# sim800L_5.net
KiCad netlist of a schematic drawn in EAGLE
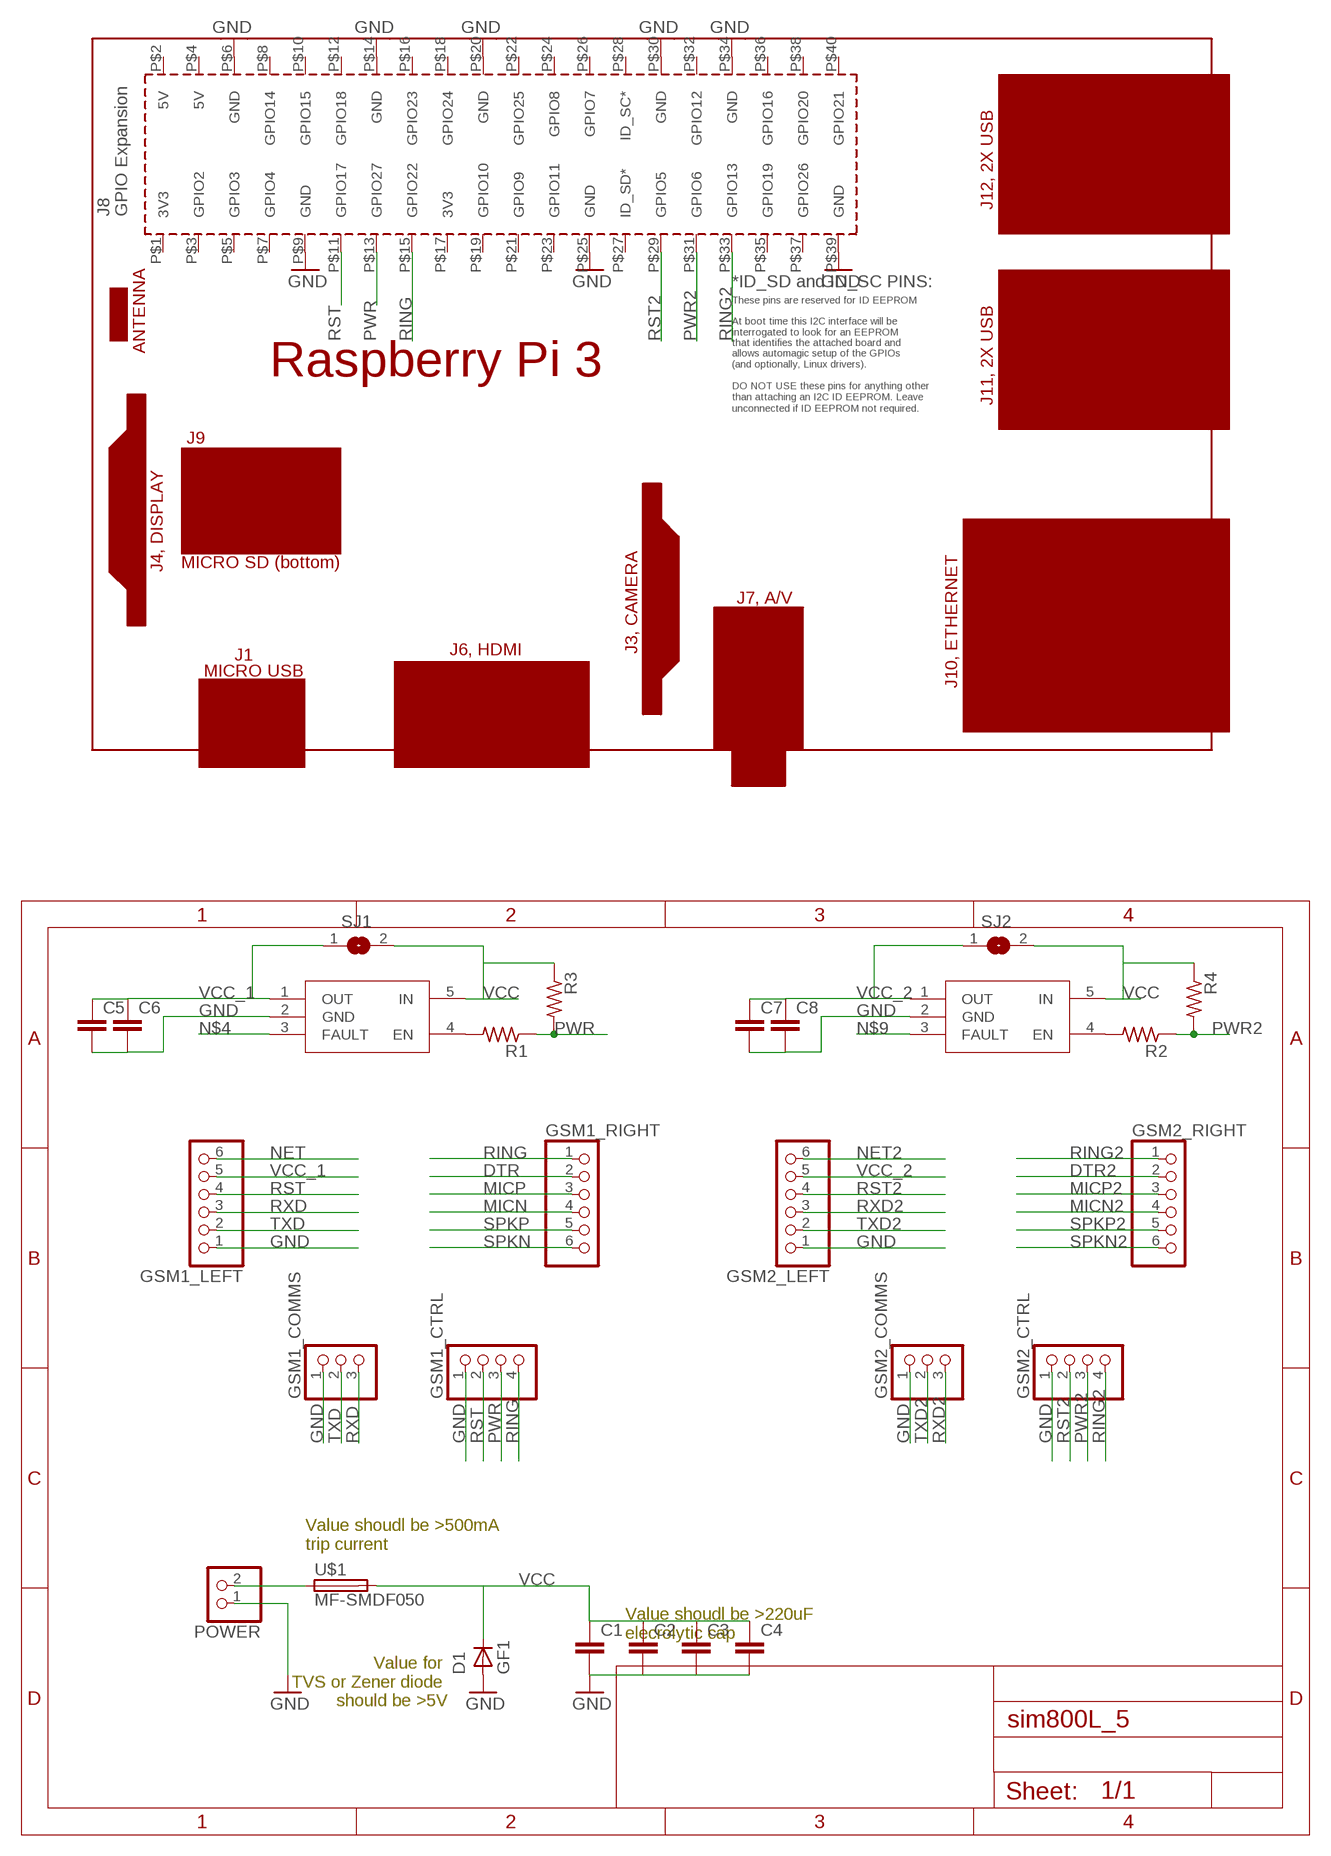
[diagram p0: schematic, sheet 1]

(export (version "E")
  (design (tool "Eeschema 10.0.6"))
  (components
    (comp (ref "C1")
      (value "C-EUC1210")
      (footprint "eagle-import:C1210")
      (libsource (lib "eagle-import") (part "C-EUC1210"))
    )
    (comp (ref "C2")
      (value "C-EUC1210")
      (footprint "eagle-import:C1210")
      (libsource (lib "eagle-import") (part "C-EUC1210"))
    )
    (comp (ref "C3")
      (value "C-EUC1210")
      (footprint "eagle-import:C1210")
      (libsource (lib "eagle-import") (part "C-EUC1210"))
    )
    (comp (ref "C4")
      (value "C-EUC1210")
      (footprint "eagle-import:C1210")
      (libsource (lib "eagle-import") (part "C-EUC1210"))
    )
    (comp (ref "C5")
      (value "C-EUC4532")
      (footprint "eagle-import:C4532")
      (libsource (lib "eagle-import") (part "C-EUC4532"))
    )
    (comp (ref "C6")
      (value "C-EUC4532")
      (footprint "eagle-import:C4532")
      (libsource (lib "eagle-import") (part "C-EUC4532"))
    )
    (comp (ref "C7")
      (value "C-EUC4532")
      (footprint "eagle-import:C4532")
      (libsource (lib "eagle-import") (part "C-EUC4532"))
    )
    (comp (ref "C8")
      (value "C-EUC4532")
      (footprint "eagle-import:C4532")
      (libsource (lib "eagle-import") (part "C-EUC4532"))
    )
    (comp (ref "D1")
      (value "GF1")
      (footprint "eagle-import:SMA-DO214AC")
      (libsource (lib "eagle-import") (part "GF1"))
    )
    (comp (ref "GSM1_COMMS")
      (value "PINHD-1X3")
      (footprint "eagle-import:1X03")
      (libsource (lib "eagle-import") (part "PINHD-1X3"))
    )
    (comp (ref "GSM1_CTRL")
      (value "PINHD-1X4")
      (footprint "eagle-import:1X04")
      (libsource (lib "eagle-import") (part "PINHD-1X4"))
    )
    (comp (ref "GSM1_LEFT")
      (value "PINHD-1X6")
      (footprint "eagle-import:1X06")
      (libsource (lib "eagle-import") (part "PINHD-1X6"))
    )
    (comp (ref "GSM1_RIGHT")
      (value "PINHD-1X6")
      (footprint "eagle-import:1X06")
      (libsource (lib "eagle-import") (part "PINHD-1X6"))
    )
    (comp (ref "GSM2_COMMS")
      (value "PINHD-1X3")
      (footprint "eagle-import:1X03")
      (libsource (lib "eagle-import") (part "PINHD-1X3"))
    )
    (comp (ref "GSM2_CTRL")
      (value "PINHD-1X4")
      (footprint "eagle-import:1X04")
      (libsource (lib "eagle-import") (part "PINHD-1X4"))
    )
    (comp (ref "GSM2_LEFT")
      (value "PINHD-1X6")
      (footprint "eagle-import:1X06")
      (libsource (lib "eagle-import") (part "PINHD-1X6"))
    )
    (comp (ref "GSM2_RIGHT")
      (value "PINHD-1X6")
      (footprint "eagle-import:1X06")
      (libsource (lib "eagle-import") (part "PINHD-1X6"))
    )
    (comp (ref "POWER")
      (value "PINHD-1X2")
      (footprint "eagle-import:1X02")
      (libsource (lib "eagle-import") (part "PINHD-1X2"))
    )
    (comp (ref "R1")
      (value "R-US_R0805")
      (footprint "eagle-import:R0805")
      (libsource (lib "eagle-import") (part "R-US_R0805"))
    )
    (comp (ref "R2")
      (value "R-US_R0805")
      (footprint "eagle-import:R0805")
      (libsource (lib "eagle-import") (part "R-US_R0805"))
    )
    (comp (ref "R3")
      (value "R-US_R0805")
      (footprint "eagle-import:R0805")
      (libsource (lib "eagle-import") (part "R-US_R0805"))
    )
    (comp (ref "R4")
      (value "R-US_R0805")
      (footprint "eagle-import:R0805")
      (libsource (lib "eagle-import") (part "R-US_R0805"))
    )
    (comp (ref "SJ1") (value "SJ") (footprint "eagle-import:SJ") (libsource (lib "eagle-import") (part "SJ")))
    (comp (ref "SJ2") (value "SJ") (footprint "eagle-import:SJ") (libsource (lib "eagle-import") (part "SJ")))
    (comp (ref "U$1")
      (value "MF-SMDF050")
      (footprint "eagle-import:MF-SMDF050")
      (libsource (lib "eagle-import") (part "MF-SMDF050"))
    )
    (comp (ref "U$2")
      (value "RPI3_SHIELD")
      (footprint "eagle-import:RPI3_SHIELD")
      (libsource (lib "eagle-import") (part "RPI3_SHIELD"))
    )
    (comp (ref "U$3")
      (value "STMPS2161STR")
      (footprint "eagle-import:SOT23-5L")
      (libsource (lib "eagle-import") (part "STMPS2161STR"))
    )
    (comp (ref "U$4")
      (value "STMPS2161STR")
      (footprint "eagle-import:SOT23-5L")
      (libsource (lib "eagle-import") (part "STMPS2161STR"))
    )
  )
  (nets
    (net (code "1") (name "/DTR") (class "Default")
      (node (ref "GSM1_RIGHT") (pin "2") (pinfunction "2_2") (pintype "passive"))
    )
    (net (code "2") (name "/DTR2") (class "Default")
      (node (ref "GSM2_RIGHT") (pin "2") (pinfunction "2_2") (pintype "passive"))
    )
    (net (code "3") (name "/MICN") (class "Default")
      (node (ref "GSM1_RIGHT") (pin "4") (pinfunction "4_4") (pintype "passive"))
    )
    (net (code "4") (name "/MICN2") (class "Default")
      (node (ref "GSM2_RIGHT") (pin "4") (pinfunction "4_4") (pintype "passive"))
    )
    (net (code "5") (name "/MICP") (class "Default")
      (node (ref "GSM1_RIGHT") (pin "3") (pinfunction "3_3") (pintype "passive"))
    )
    (net (code "6") (name "/MICP2") (class "Default")
      (node (ref "GSM2_RIGHT") (pin "3") (pinfunction "3_3") (pintype "passive"))
    )
    (net (code "7") (name "/N$4") (class "Default")
      (node (ref "U$4") (pin "3") (pinfunction "FAULT_3") (pintype "bidirectional"))
    )
    (net (code "8") (name "/N$9") (class "Default")
      (node (ref "U$3") (pin "3") (pinfunction "FAULT_3") (pintype "bidirectional"))
    )
    (net (code "9") (name "/NET") (class "Default")
      (node (ref "GSM1_LEFT") (pin "6") (pinfunction "6_6") (pintype "passive"))
    )
    (net (code "10") (name "/NET2") (class "Default")
      (node (ref "GSM2_LEFT") (pin "6") (pinfunction "6_6") (pintype "passive"))
    )
    (net (code "11") (name "/PWR") (class "Default")
      (node (ref "GSM1_CTRL") (pin "3") (pinfunction "3_3") (pintype "passive"))
      (node (ref "R1") (pin "1") (pinfunction "1_1") (pintype "passive"))
      (node (ref "R3") (pin "2") (pinfunction "2_2") (pintype "passive"))
      (node (ref "U$2") (pin "P$13") (pinfunction "GPIO27_P$13") (pintype "bidirectional"))
    )
    (net (code "12") (name "/PWR2") (class "Default")
      (node (ref "GSM2_CTRL") (pin "3") (pinfunction "3_3") (pintype "passive"))
      (node (ref "R2") (pin "1") (pinfunction "1_1") (pintype "passive"))
      (node (ref "R4") (pin "2") (pinfunction "2_2") (pintype "passive"))
      (node (ref "U$2") (pin "P$31") (pinfunction "GPIO6_P$31") (pintype "bidirectional"))
    )
    (net (code "13") (name "/RING") (class "Default")
      (node (ref "GSM1_CTRL") (pin "4") (pinfunction "4_4") (pintype "passive"))
      (node (ref "GSM1_RIGHT") (pin "1") (pinfunction "1_1") (pintype "passive"))
      (node (ref "U$2") (pin "P$15") (pinfunction "GPIO22_P$15") (pintype "bidirectional"))
    )
    (net (code "14") (name "/RING2") (class "Default")
      (node (ref "GSM2_CTRL") (pin "4") (pinfunction "4_4") (pintype "passive"))
      (node (ref "GSM2_RIGHT") (pin "1") (pinfunction "1_1") (pintype "passive"))
      (node (ref "U$2") (pin "P$33") (pinfunction "GPIO13_P$33") (pintype "bidirectional"))
    )
    (net (code "15") (name "/RST") (class "Default")
      (node (ref "GSM1_CTRL") (pin "2") (pinfunction "2_2") (pintype "passive"))
      (node (ref "GSM1_LEFT") (pin "4") (pinfunction "4_4") (pintype "passive"))
      (node (ref "U$2") (pin "P$11") (pinfunction "GPIO17_P$11") (pintype "bidirectional"))
    )
    (net (code "16") (name "/RST2") (class "Default")
      (node (ref "GSM2_CTRL") (pin "2") (pinfunction "2_2") (pintype "passive"))
      (node (ref "GSM2_LEFT") (pin "4") (pinfunction "4_4") (pintype "passive"))
      (node (ref "U$2") (pin "P$29") (pinfunction "GPIO5_P$29") (pintype "bidirectional"))
    )
    (net (code "17") (name "/RXD") (class "Default")
      (node (ref "GSM1_COMMS") (pin "3") (pinfunction "3_3") (pintype "passive"))
      (node (ref "GSM1_LEFT") (pin "3") (pinfunction "3_3") (pintype "passive"))
    )
    (net (code "18") (name "/RXD2") (class "Default")
      (node (ref "GSM2_COMMS") (pin "3") (pinfunction "3_3") (pintype "passive"))
      (node (ref "GSM2_LEFT") (pin "3") (pinfunction "3_3") (pintype "passive"))
    )
    (net (code "19") (name "/SPKN") (class "Default")
      (node (ref "GSM1_RIGHT") (pin "6") (pinfunction "6_6") (pintype "passive"))
    )
    (net (code "20") (name "/SPKN2") (class "Default")
      (node (ref "GSM2_RIGHT") (pin "6") (pinfunction "6_6") (pintype "passive"))
    )
    (net (code "21") (name "/SPKP") (class "Default")
      (node (ref "GSM1_RIGHT") (pin "5") (pinfunction "5_5") (pintype "passive"))
    )
    (net (code "22") (name "/SPKP2") (class "Default")
      (node (ref "GSM2_RIGHT") (pin "5") (pinfunction "5_5") (pintype "passive"))
    )
    (net (code "23") (name "/TXD") (class "Default")
      (node (ref "GSM1_COMMS") (pin "2") (pinfunction "2_2") (pintype "passive"))
      (node (ref "GSM1_LEFT") (pin "2") (pinfunction "2_2") (pintype "passive"))
    )
    (net (code "24") (name "/TXD2") (class "Default")
      (node (ref "GSM2_COMMS") (pin "2") (pinfunction "2_2") (pintype "passive"))
      (node (ref "GSM2_LEFT") (pin "2") (pinfunction "2_2") (pintype "passive"))
    )
    (net (code "25") (name "/VCC") (class "Default")
      (node (ref "C1") (pin "1") (pinfunction "1_1") (pintype "passive"))
      (node (ref "C2") (pin "1") (pinfunction "1_1") (pintype "passive"))
      (node (ref "C3") (pin "1") (pinfunction "1_1") (pintype "passive"))
      (node (ref "C4") (pin "1") (pinfunction "1_1") (pintype "passive"))
      (node (ref "D1") (pin "K") (pinfunction "C_K") (pintype "passive"))
      (node (ref "R3") (pin "1") (pinfunction "1_1") (pintype "passive"))
      (node (ref "R4") (pin "1") (pinfunction "1_1") (pintype "passive"))
      (node (ref "SJ1") (pin "2") (pinfunction "2_2") (pintype "passive"))
      (node (ref "SJ2") (pin "2") (pinfunction "2_2") (pintype "passive"))
      (node (ref "U$1") (pin "2") (pinfunction "2_2") (pintype "passive"))
      (node (ref "U$3") (pin "5") (pinfunction "IN_5") (pintype "bidirectional"))
      (node (ref "U$4") (pin "5") (pinfunction "IN_5") (pintype "bidirectional"))
    )
    (net (code "26") (name "/VCC_1") (class "Default")
      (node (ref "C5") (pin "1") (pinfunction "1_1") (pintype "passive"))
      (node (ref "C6") (pin "1") (pinfunction "1_1") (pintype "passive"))
      (node (ref "GSM1_LEFT") (pin "5") (pinfunction "5_5") (pintype "passive"))
      (node (ref "SJ1") (pin "1") (pinfunction "1_1") (pintype "passive"))
      (node (ref "U$4") (pin "1") (pinfunction "OUT_1") (pintype "bidirectional"))
    )
    (net (code "27") (name "/VCC_2") (class "Default")
      (node (ref "C7") (pin "1") (pinfunction "1_1") (pintype "passive"))
      (node (ref "C8") (pin "1") (pinfunction "1_1") (pintype "passive"))
      (node (ref "GSM2_LEFT") (pin "5") (pinfunction "5_5") (pintype "passive"))
      (node (ref "SJ2") (pin "1") (pinfunction "1_1") (pintype "passive"))
      (node (ref "U$3") (pin "1") (pinfunction "OUT_1") (pintype "bidirectional"))
    )
    (net (code "28") (name "GND") (class "Default")
      (node (ref "C1") (pin "2") (pinfunction "2_2") (pintype "passive"))
      (node (ref "C2") (pin "2") (pinfunction "2_2") (pintype "passive"))
      (node (ref "C3") (pin "2") (pinfunction "2_2") (pintype "passive"))
      (node (ref "C4") (pin "2") (pinfunction "2_2") (pintype "passive"))
      (node (ref "C5") (pin "2") (pinfunction "2_2") (pintype "passive"))
      (node (ref "C6") (pin "2") (pinfunction "2_2") (pintype "passive"))
      (node (ref "C7") (pin "2") (pinfunction "2_2") (pintype "passive"))
      (node (ref "C8") (pin "2") (pinfunction "2_2") (pintype "passive"))
      (node (ref "D1") (pin "A") (pinfunction "A_A") (pintype "passive"))
      (node (ref "GSM1_COMMS") (pin "1") (pinfunction "1_1") (pintype "passive"))
      (node (ref "GSM1_CTRL") (pin "1") (pinfunction "1_1") (pintype "passive"))
      (node (ref "GSM1_LEFT") (pin "1") (pinfunction "1_1") (pintype "passive"))
      (node (ref "GSM2_COMMS") (pin "1") (pinfunction "1_1") (pintype "passive"))
      (node (ref "GSM2_CTRL") (pin "1") (pinfunction "1_1") (pintype "passive"))
      (node (ref "GSM2_LEFT") (pin "1") (pinfunction "1_1") (pintype "passive"))
      (node (ref "POWER") (pin "1") (pinfunction "1_1") (pintype "passive"))
      (node (ref "U$2") (pin "P$14") (pinfunction "GND_P$14") (pintype "bidirectional"))
      (node (ref "U$2") (pin "P$20") (pinfunction "GND_P$20") (pintype "bidirectional"))
      (node (ref "U$2") (pin "P$25") (pinfunction "GND_P$25") (pintype "bidirectional"))
      (node (ref "U$2") (pin "P$30") (pinfunction "GND_P$30") (pintype "bidirectional"))
      (node (ref "U$2") (pin "P$34") (pinfunction "GND_P$34") (pintype "bidirectional"))
      (node (ref "U$2") (pin "P$39") (pinfunction "GND_P$39") (pintype "bidirectional"))
      (node (ref "U$2") (pin "P$6") (pinfunction "GND_P$6") (pintype "bidirectional"))
      (node (ref "U$2") (pin "P$9") (pinfunction "GND_P$9") (pintype "bidirectional"))
      (node (ref "U$3") (pin "2") (pinfunction "GND_2") (pintype "bidirectional"))
      (node (ref "U$4") (pin "2") (pinfunction "GND_2") (pintype "bidirectional"))
    )
    (net (code "29") (name "Net-(POWER-Pad2)") (class "Default")
      (node (ref "POWER") (pin "2") (pinfunction "2_2") (pintype "passive"))
      (node (ref "U$1") (pin "1") (pinfunction "1_1") (pintype "passive"))
    )
    (net (code "30") (name "Net-(U$3-EN)") (class "Default")
      (node (ref "R2") (pin "2") (pinfunction "2_2") (pintype "passive"))
      (node (ref "U$3") (pin "4") (pinfunction "EN_4") (pintype "bidirectional"))
    )
    (net (code "31") (name "Net-(U$4-EN)") (class "Default")
      (node (ref "R1") (pin "2") (pinfunction "2_2") (pintype "passive"))
      (node (ref "U$4") (pin "4") (pinfunction "EN_4") (pintype "bidirectional"))
    )
    (net (code "32") (name "unconnected-(U$2-3V3-PadP$1)") (class "Default")
      (node (ref "U$2") (pin "P$1") (pinfunction "3V3_P$1") (pintype "bidirectional"))
    )
    (net (code "33") (name "unconnected-(U$2-3V3-PadP$17)") (class "Default")
      (node (ref "U$2") (pin "P$17") (pinfunction "3V3_P$17") (pintype "bidirectional"))
    )
    (net (code "34") (name "unconnected-(U$2-5V-PadP$2)") (class "Default")
      (node (ref "U$2") (pin "P$2") (pinfunction "5V_P$2") (pintype "bidirectional"))
    )
    (net (code "35") (name "unconnected-(U$2-5V-PadP$4)") (class "Default")
      (node (ref "U$2") (pin "P$4") (pinfunction "5V_P$4") (pintype "bidirectional"))
    )
    (net (code "36") (name "unconnected-(U$2-GPIO2-PadP$3)") (class "Default")
      (node (ref "U$2") (pin "P$3") (pinfunction "GPIO2_P$3") (pintype "bidirectional"))
    )
    (net (code "37") (name "unconnected-(U$2-GPIO3-PadP$5)") (class "Default")
      (node (ref "U$2") (pin "P$5") (pinfunction "GPIO3_P$5") (pintype "bidirectional"))
    )
    (net (code "38") (name "unconnected-(U$2-GPIO4-PadP$7)") (class "Default")
      (node (ref "U$2") (pin "P$7") (pinfunction "GPIO4_P$7") (pintype "bidirectional"))
    )
    (net (code "39") (name "unconnected-(U$2-GPIO7-PadP$26)") (class "Default")
      (node (ref "U$2") (pin "P$26") (pinfunction "GPIO7_P$26") (pintype "bidirectional"))
    )
    (net (code "40") (name "unconnected-(U$2-GPIO8-PadP$24)") (class "Default")
      (node (ref "U$2") (pin "P$24") (pinfunction "GPIO8_P$24") (pintype "bidirectional"))
    )
    (net (code "41") (name "unconnected-(U$2-GPIO9-PadP$21)") (class "Default")
      (node (ref "U$2") (pin "P$21") (pinfunction "GPIO9_P$21") (pintype "bidirectional"))
    )
    (net (code "42") (name "unconnected-(U$2-GPIO10-PadP$19)") (class "Default")
      (node (ref "U$2") (pin "P$19") (pinfunction "GPIO10_P$19") (pintype "bidirectional"))
    )
    (net (code "43") (name "unconnected-(U$2-GPIO11-PadP$23)") (class "Default")
      (node (ref "U$2") (pin "P$23") (pinfunction "GPIO11_P$23") (pintype "bidirectional"))
    )
    (net (code "44") (name "unconnected-(U$2-GPIO12-PadP$32)") (class "Default")
      (node (ref "U$2") (pin "P$32") (pinfunction "GPIO12_P$32") (pintype "bidirectional"))
    )
    (net (code "45") (name "unconnected-(U$2-GPIO14-PadP$8)") (class "Default")
      (node (ref "U$2") (pin "P$8") (pinfunction "GPIO14_P$8") (pintype "bidirectional"))
    )
    (net (code "46") (name "unconnected-(U$2-GPIO15-PadP$10)") (class "Default")
      (node (ref "U$2") (pin "P$10") (pinfunction "GPIO15_P$10") (pintype "bidirectional"))
    )
    (net (code "47") (name "unconnected-(U$2-GPIO16-PadP$36)") (class "Default")
      (node (ref "U$2") (pin "P$36") (pinfunction "GPIO16_P$36") (pintype "bidirectional"))
    )
    (net (code "48") (name "unconnected-(U$2-GPIO18-PadP$12)") (class "Default")
      (node (ref "U$2") (pin "P$12") (pinfunction "GPIO18_P$12") (pintype "bidirectional"))
    )
    (net (code "49") (name "unconnected-(U$2-GPIO19-PadP$35)") (class "Default")
      (node (ref "U$2") (pin "P$35") (pinfunction "GPIO19_P$35") (pintype "bidirectional"))
    )
    (net (code "50") (name "unconnected-(U$2-GPIO20-PadP$38)") (class "Default")
      (node (ref "U$2") (pin "P$38") (pinfunction "GPIO20_P$38") (pintype "bidirectional"))
    )
    (net (code "51") (name "unconnected-(U$2-GPIO21-PadP$40)") (class "Default")
      (node (ref "U$2") (pin "P$40") (pinfunction "GPIO21_P$40") (pintype "bidirectional"))
    )
    (net (code "52") (name "unconnected-(U$2-GPIO23-PadP$16)") (class "Default")
      (node (ref "U$2") (pin "P$16") (pinfunction "GPIO23_P$16") (pintype "bidirectional"))
    )
    (net (code "53") (name "unconnected-(U$2-GPIO24-PadP$18)") (class "Default")
      (node (ref "U$2") (pin "P$18") (pinfunction "GPIO24_P$18") (pintype "bidirectional"))
    )
    (net (code "54") (name "unconnected-(U$2-GPIO25-PadP$22)") (class "Default")
      (node (ref "U$2") (pin "P$22") (pinfunction "GPIO25_P$22") (pintype "bidirectional"))
    )
    (net (code "55") (name "unconnected-(U$2-GPIO26-PadP$37)") (class "Default")
      (node (ref "U$2") (pin "P$37") (pinfunction "GPIO26_P$37") (pintype "bidirectional"))
    )
    (net (code "56") (name "unconnected-(U$2-ID_SC*-PadP$28)") (class "Default")
      (node (ref "U$2") (pin "P$28") (pinfunction "ID_SC*_P$28") (pintype "bidirectional"))
    )
    (net (code "57") (name "unconnected-(U$2-ID_SD*-PadP$27)") (class "Default")
      (node (ref "U$2") (pin "P$27") (pinfunction "ID_SD*_P$27") (pintype "bidirectional"))
    )
  )
)
